# Dosyn.net
KiCad netlist of a schematic drawn in Altium Designer
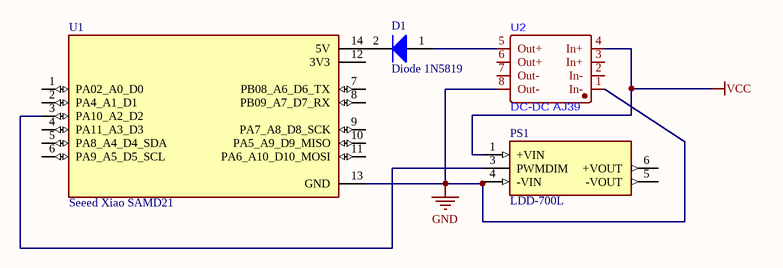
[diagram p0: Dosyn.SchDoc]

(export (version "E")
  (design (tool "Eeschema 10.0.6"))
  (components
    (comp (ref "D1")
      (value "Diode 1N5819")
      (footprint "DO-214AC/SMA")
      (description "3 Amp Medium Power Silicon Rectifier Diode")
      (fields (field (name "PUBLISHER") "Altium Limited"))
      (libsource (lib "Miscellaneous Devices") (part "Diode 1N5408"))
    )
    (comp (ref "PS1")
      (value "LDD-700L")
      (footprint "SamacSys:LDD-XXXL")
      (description "Power Supply")
      (fields (field (name "MOUSER PART NUMBER") "709-LDD-700L"))
      (libsource (lib "SamacSys") (part "LDD-700L"))
    )
    (comp (ref "U1")
      (value "Seeed Xiao SAMD21")
      (footprint "MODULE_102010388")
      (fields (field (name "MP") "102010388") (field (name "MF") "Seeed Technology Co., Ltd"))
      (libsource (lib "Seeed Xiao SMD21") (part "102010388"))
    )
    (comp (ref "U2")
      (value "DC-DC AJ39")
      (footprint "DC-DC-AJ39")
      (description "36V in 5V out")
      (libsource (lib "DC-DC-AJ39") (part "DC-DC AJ39"))
    )
  )
  (nets
    (net (code "1") (name "GND") (class "Default")
      (node (ref "PS1") (pin "4") (pinfunction "-VIN_4") (pintype "input"))
      (node (ref "U1") (pin "13") (pinfunction "GND_13") (pintype "power_in"))
      (node (ref "U2") (pin "1") (pinfunction "In-_1") (pintype "passive"))
      (node (ref "U2") (pin "8") (pinfunction "Out-_8") (pintype "passive"))
    )
    (net (code "2") (name "Net-(D1-Pad1)") (class "Default")
      (node (ref "D1") (pin "1") (pinfunction "1_1") (pintype "passive"))
      (node (ref "U2") (pin "5") (pinfunction "Out+_5") (pintype "passive"))
    )
    (net (code "3") (name "Net-(PS1-PWMDIM)") (class "Default")
      (node (ref "PS1") (pin "3") (pinfunction "PWMDIM_3") (pintype "passive"))
      (node (ref "U1") (pin "3") (pinfunction "PA10_A2_D2_3") (pintype "bidirectional"))
    )
    (net (code "4") (name "Net-(U1-5V)") (class "Default")
      (node (ref "D1") (pin "2") (pinfunction "2_2") (pintype "passive"))
      (node (ref "U1") (pin "14") (pinfunction "5V_14") (pintype "power_in"))
    )
    (net (code "5") (name "VCC") (class "Default")
      (node (ref "PS1") (pin "1") (pinfunction "+VIN_1") (pintype "input"))
      (node (ref "U2") (pin "4") (pinfunction "In+_4") (pintype "passive"))
    )
    (net (code "6") (name "unconnected-(PS1-+VOUT-Pad6)") (class "Default")
      (node (ref "PS1") (pin "6") (pinfunction "+VOUT_6") (pintype "output"))
    )
    (net (code "7") (name "unconnected-(PS1--VOUT-Pad5)") (class "Default")
      (node (ref "PS1") (pin "5") (pinfunction "-VOUT_5") (pintype "output"))
    )
    (net (code "8") (name "unconnected-(U1-3V3-Pad12)") (class "Default")
      (node (ref "U1") (pin "12") (pinfunction "3V3_12") (pintype "power_in"))
    )
    (net (code "9") (name "unconnected-(U1-PA02_A0_D0-Pad1)") (class "Default")
      (node (ref "U1") (pin "1") (pinfunction "PA02_A0_D0_1") (pintype "bidirectional"))
    )
    (net (code "10") (name "unconnected-(U1-PA4_A1_D1-Pad2)") (class "Default")
      (node (ref "U1") (pin "2") (pinfunction "PA4_A1_D1_2") (pintype "bidirectional"))
    )
    (net (code "11") (name "unconnected-(U1-PA5_A9_D9_MISO-Pad10)") (class "Default")
      (node (ref "U1") (pin "10") (pinfunction "PA5_A9_D9_MISO_10") (pintype "bidirectional"))
    )
    (net (code "12") (name "unconnected-(U1-PA6_A10_D10_MOSI-Pad11)") (class "Default")
      (node (ref "U1") (pin "11") (pinfunction "PA6_A10_D10_MOSI_11") (pintype "bidirectional"))
    )
    (net (code "13") (name "unconnected-(U1-PA7_A8_D8_SCK-Pad9)") (class "Default")
      (node (ref "U1") (pin "9") (pinfunction "PA7_A8_D8_SCK_9") (pintype "bidirectional"))
    )
    (net (code "14") (name "unconnected-(U1-PA8_A4_D4_SDA-Pad5)") (class "Default")
      (node (ref "U1") (pin "5") (pinfunction "PA8_A4_D4_SDA_5") (pintype "bidirectional"))
    )
    (net (code "15") (name "unconnected-(U1-PA9_A5_D5_SCL-Pad6)") (class "Default")
      (node (ref "U1") (pin "6") (pinfunction "PA9_A5_D5_SCL_6") (pintype "bidirectional"))
    )
    (net (code "16") (name "unconnected-(U1-PA11_A3_D3-Pad4)") (class "Default")
      (node (ref "U1") (pin "4") (pinfunction "PA11_A3_D3_4") (pintype "bidirectional"))
    )
    (net (code "17") (name "unconnected-(U1-PB08_A6_D6_TX-Pad7)") (class "Default")
      (node (ref "U1") (pin "7") (pinfunction "PB08_A6_D6_TX_7") (pintype "bidirectional"))
    )
    (net (code "18") (name "unconnected-(U1-PB09_A7_D7_RX-Pad8)") (class "Default")
      (node (ref "U1") (pin "8") (pinfunction "PB09_A7_D7_RX_8") (pintype "bidirectional"))
    )
    (net (code "19") (name "unconnected-(U2-In+-Pad3)") (class "Default")
      (node (ref "U2") (pin "3") (pinfunction "In+_3") (pintype "passive"))
    )
    (net (code "20") (name "unconnected-(U2-In--Pad2)") (class "Default")
      (node (ref "U2") (pin "2") (pinfunction "In-_2") (pintype "passive"))
    )
    (net (code "21") (name "unconnected-(U2-Out+-Pad6)") (class "Default")
      (node (ref "U2") (pin "6") (pinfunction "Out+_6") (pintype "passive"))
    )
    (net (code "22") (name "unconnected-(U2-Out--Pad7)") (class "Default")
      (node (ref "U2") (pin "7") (pinfunction "Out-_7") (pintype "passive"))
    )
  )
)
